# programmer.net
KiCad netlist of a schematic drawn in Altium Designer
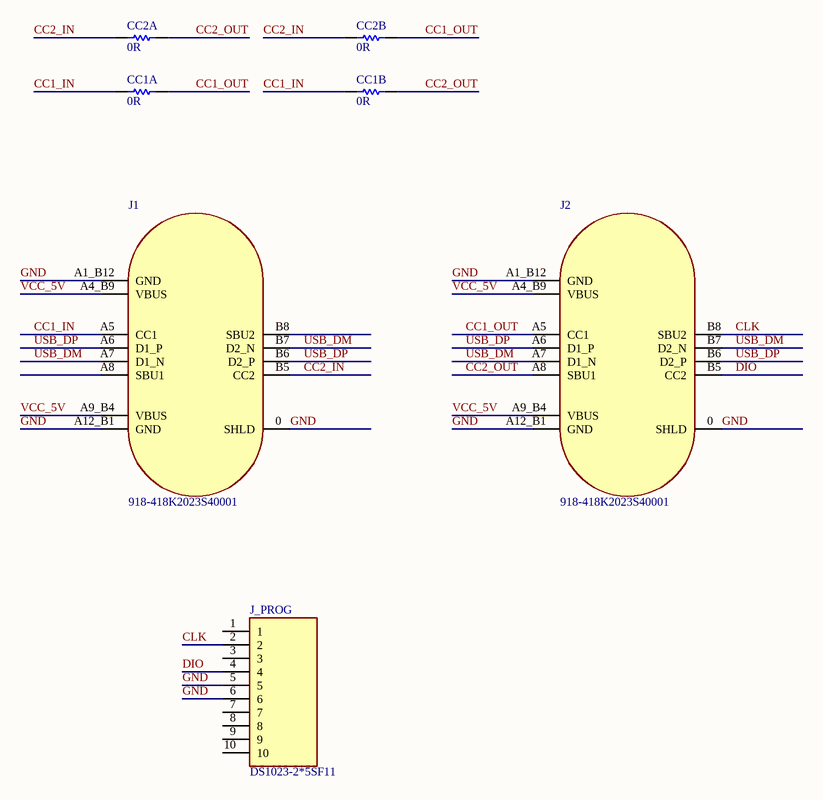
[diagram p0: programmer.SchDoc]

(export (version "E")
  (design (tool "Eeschema 10.0.6"))
  (components
    (comp (ref "CC1A")
      (value "0R")
      (footprint "R_0402")
      (description "R - RESISTOR - SMD - 0R - 1% - 0402")
      (fields (field (name "LCSC PART #") "C17168") (field (name "Comment") "0402WGF0000TCE"))
      (libsource (lib "JLC_PCB") (part "0402WGF0000TCE"))
    )
    (comp (ref "CC1B")
      (value "0R")
      (footprint "R_0402")
      (description "R - RESISTOR - SMD - 0R - 1% - 0402")
      (fields (field (name "LCSC PART #") "C17168") (field (name "Comment") "0402WGF0000TCE"))
      (libsource (lib "JLC_PCB") (part "0402WGF0000TCE"))
    )
    (comp (ref "CC2A")
      (value "0R")
      (footprint "R_0402")
      (description "R - RESISTOR - SMD - 0R - 1% - 0402")
      (fields (field (name "LCSC PART #") "C17168") (field (name "Comment") "0402WGF0000TCE"))
      (libsource (lib "JLC_PCB") (part "0402WGF0000TCE"))
    )
    (comp (ref "CC2B")
      (value "0R")
      (footprint "R_0402")
      (description "R - RESISTOR - SMD - 0R - 1% - 0402")
      (fields (field (name "LCSC PART #") "C17168") (field (name "Comment") "0402WGF0000TCE"))
      (libsource (lib "JLC_PCB") (part "0402WGF0000TCE"))
    )
    (comp (ref "J1")
      (value "918-418K2023S40001")
      (footprint "DX07S016JA1R1500")
      (description "J - JACK - USB - Type C - Recepticle - SMT - 90°")
      (fields (field (name "LCSC PART #") "C167321"))
      (libsource (lib "JLC_PCB") (part "918-418K2023S40001"))
    )
    (comp (ref "J2")
      (value "918-418K2023S40001")
      (footprint "DX07S016JA1R1500")
      (description "J - JACK - USB - Type C - Recepticle - SMT - 90°")
      (fields (field (name "LCSC PART #") "C167321"))
      (libsource (lib "JLC_PCB") (part "918-418K2023S40001"))
    )
    (comp (ref "J_PROG")
      (value "DS1023-2*5SF11")
      (footprint "HDR_FEM_2X5P")
      (description "J - JACK - PIN_HEADER 2X5P")
      (fields (field (name "LCSC PART #") "C125068"))
      (libsource (lib "JLC_PCB") (part "DS1023-2*5SF11"))
    )
  )
  (nets
    (net (code "1") (name "/CC1_IN") (class "Default")
      (node (ref "CC1A") (pin "1") (pinfunction "1_1") (pintype "passive"))
      (node (ref "CC1B") (pin "1") (pinfunction "1_1") (pintype "passive"))
      (node (ref "J1") (pin "A5") (pinfunction "CC1_A5") (pintype "passive"))
    )
    (net (code "2") (name "/CC1_OUT") (class "Default")
      (node (ref "CC1A") (pin "2") (pinfunction "2_2") (pintype "passive"))
      (node (ref "CC2B") (pin "2") (pinfunction "2_2") (pintype "passive"))
      (node (ref "J2") (pin "A5") (pinfunction "CC1_A5") (pintype "passive"))
    )
    (net (code "3") (name "/CC2_IN") (class "Default")
      (node (ref "CC2A") (pin "1") (pinfunction "1_1") (pintype "passive"))
      (node (ref "CC2B") (pin "1") (pinfunction "1_1") (pintype "passive"))
      (node (ref "J1") (pin "B5") (pinfunction "CC2_B5") (pintype "passive"))
    )
    (net (code "4") (name "/CC2_OUT") (class "Default")
      (node (ref "CC1B") (pin "2") (pinfunction "2_2") (pintype "passive"))
      (node (ref "CC2A") (pin "2") (pinfunction "2_2") (pintype "passive"))
      (node (ref "J2") (pin "A8") (pinfunction "SBU1_A8") (pintype "passive"))
    )
    (net (code "5") (name "/CLK") (class "Default")
      (node (ref "J2") (pin "B8") (pinfunction "SBU2_B8") (pintype "passive"))
      (node (ref "J_PROG") (pin "2") (pinfunction "2_2") (pintype "passive"))
    )
    (net (code "6") (name "/DIO") (class "Default")
      (node (ref "J2") (pin "B5") (pinfunction "CC2_B5") (pintype "passive"))
      (node (ref "J_PROG") (pin "4") (pinfunction "4_4") (pintype "passive"))
    )
    (net (code "7") (name "/GND") (class "Default")
      (node (ref "J1") (pin "0") (pinfunction "SHLD_0") (pintype "passive"))
      (node (ref "J1") (pin "A12_B1") (pinfunction "GND_A12_B1") (pintype "passive"))
      (node (ref "J1") (pin "A1_B12") (pinfunction "GND_A1_B12") (pintype "passive"))
      (node (ref "J2") (pin "0") (pinfunction "SHLD_0") (pintype "passive"))
      (node (ref "J2") (pin "A12_B1") (pinfunction "GND_A12_B1") (pintype "passive"))
      (node (ref "J2") (pin "A1_B12") (pinfunction "GND_A1_B12") (pintype "passive"))
      (node (ref "J_PROG") (pin "5") (pinfunction "5_5") (pintype "passive"))
      (node (ref "J_PROG") (pin "6") (pinfunction "6_6") (pintype "passive"))
    )
    (net (code "8") (name "/USB_DM") (class "Default")
      (node (ref "J1") (pin "A7") (pinfunction "D1_N_A7") (pintype "passive"))
      (node (ref "J1") (pin "B7") (pinfunction "D2_N_B7") (pintype "passive"))
      (node (ref "J2") (pin "A7") (pinfunction "D1_N_A7") (pintype "passive"))
      (node (ref "J2") (pin "B7") (pinfunction "D2_N_B7") (pintype "passive"))
    )
    (net (code "9") (name "/USB_DP") (class "Default")
      (node (ref "J1") (pin "A6") (pinfunction "D1_P_A6") (pintype "passive"))
      (node (ref "J1") (pin "B6") (pinfunction "D2_P_B6") (pintype "passive"))
      (node (ref "J2") (pin "A6") (pinfunction "D1_P_A6") (pintype "passive"))
      (node (ref "J2") (pin "B6") (pinfunction "D2_P_B6") (pintype "passive"))
    )
    (net (code "10") (name "/VCC_5V") (class "Default")
      (node (ref "J1") (pin "A4_B9") (pinfunction "VBUS_A4_B9") (pintype "power_in"))
      (node (ref "J1") (pin "A9_B4") (pinfunction "VBUS_A9_B4") (pintype "power_in"))
      (node (ref "J2") (pin "A4_B9") (pinfunction "VBUS_A4_B9") (pintype "power_in"))
      (node (ref "J2") (pin "A9_B4") (pinfunction "VBUS_A9_B4") (pintype "power_in"))
    )
    (net (code "11") (name "unconnected-(J1-SBU1-PadA8)") (class "Default")
      (node (ref "J1") (pin "A8") (pinfunction "SBU1_A8") (pintype "passive"))
    )
    (net (code "12") (name "unconnected-(J1-SBU2-PadB8)") (class "Default")
      (node (ref "J1") (pin "B8") (pinfunction "SBU2_B8") (pintype "passive"))
    )
    (net (code "13") (name "unconnected-(J_PROG-Pad1)") (class "Default")
      (node (ref "J_PROG") (pin "1") (pinfunction "1_1") (pintype "passive"))
    )
    (net (code "14") (name "unconnected-(J_PROG-Pad3)") (class "Default")
      (node (ref "J_PROG") (pin "3") (pinfunction "3_3") (pintype "passive"))
    )
    (net (code "15") (name "unconnected-(J_PROG-Pad7)") (class "Default")
      (node (ref "J_PROG") (pin "7") (pinfunction "7_7") (pintype "passive"))
    )
    (net (code "16") (name "unconnected-(J_PROG-Pad8)") (class "Default")
      (node (ref "J_PROG") (pin "8") (pinfunction "8_8") (pintype "passive"))
    )
    (net (code "17") (name "unconnected-(J_PROG-Pad9)") (class "Default")
      (node (ref "J_PROG") (pin "9") (pinfunction "9_9") (pintype "passive"))
    )
    (net (code "18") (name "unconnected-(J_PROG-Pad10)") (class "Default")
      (node (ref "J_PROG") (pin "10") (pinfunction "10_10") (pintype "passive"))
    )
  )
)
